# BRAIN_3.net
KiCad netlist of a schematic drawn in EAGLE
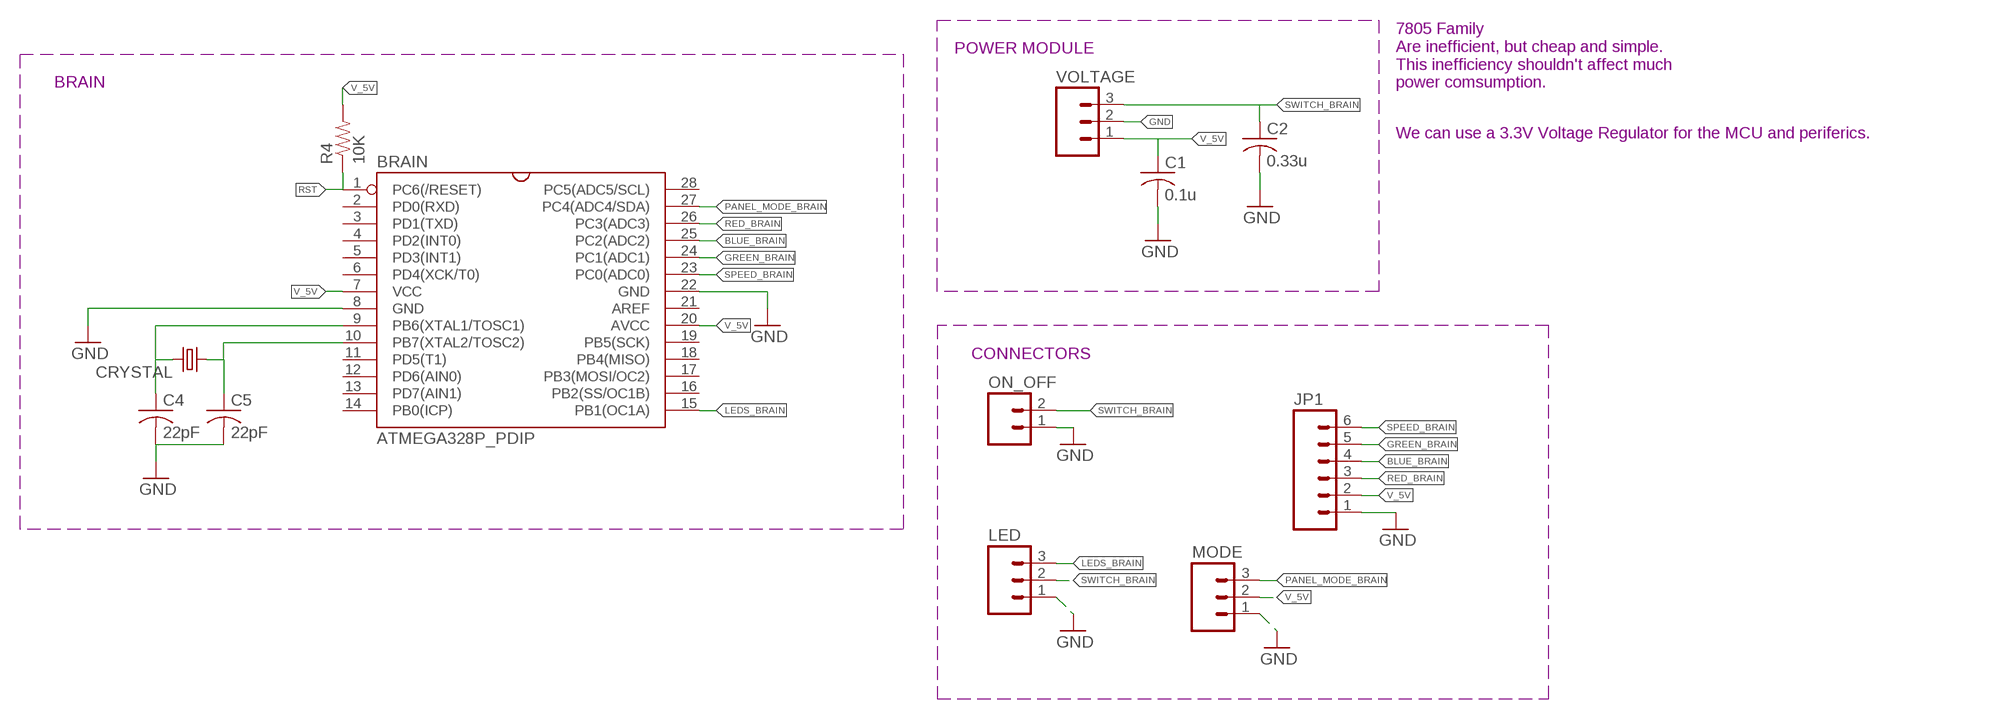
[diagram p0: schematic, sheet 1]

(export (version "E")
  (design (tool "Eeschema 10.0.6"))
  (components
    (comp (ref "BRAIN")
      (value "ATMEGA328P_PDIP")
      (footprint "eagle-import:DIL-28-3")
      (libsource (lib "eagle-import") (part "ATMEGA328P_PDIP"))
    )
    (comp (ref "C1")
      (value "0.1u")
      (footprint "eagle-import:C025-025X050")
      (libsource (lib "eagle-import") (part "C-US025-025X050"))
    )
    (comp (ref "C2")
      (value "0.33u")
      (footprint "eagle-import:C025-025X050")
      (libsource (lib "eagle-import") (part "C-US025-025X050"))
    )
    (comp (ref "C4")
      (value "22pF")
      (footprint "eagle-import:C025-024X044")
      (libsource (lib "eagle-import") (part "C-US025-024X044"))
    )
    (comp (ref "C5")
      (value "22pF")
      (footprint "eagle-import:C025-024X044")
      (libsource (lib "eagle-import") (part "C-US025-024X044"))
    )
    (comp (ref "CRYSTAL")
      (value "CRYSTALHC49US")
      (footprint "eagle-import:HC49US")
      (libsource (lib "eagle-import") (part "CRYSTALHC49US"))
    )
    (comp (ref "JP1")
      (value "M06NO_SILK_FEMALE_PTH")
      (footprint "eagle-import:1X06_NO_SILK")
      (libsource (lib "eagle-import") (part "M06NO_SILK_FEMALE_PTH"))
    )
    (comp (ref "LED")
      (value "M03PTH")
      (footprint "eagle-import:1X03")
      (libsource (lib "eagle-import") (part "M03PTH"))
    )
    (comp (ref "MODE")
      (value "M03PTH")
      (footprint "eagle-import:1X03")
      (libsource (lib "eagle-import") (part "M03PTH"))
    )
    (comp (ref "ON_OFF")
      (value "M02PTH")
      (footprint "eagle-import:1X02")
      (libsource (lib "eagle-import") (part "M02PTH"))
    )
    (comp (ref "R4")
      (value "10K")
      (footprint "eagle-import:AXIAL-0.3")
      (libsource (lib "eagle-import") (part "RESISTORAXIAL-0.3"))
    )
    (comp (ref "VOLTAGE")
      (value "M03PTH")
      (footprint "eagle-import:1X03")
      (libsource (lib "eagle-import") (part "M03PTH"))
    )
  )
  (nets
    (net (code "1") (name "BLUE_BRAIN") (class "Default")
      (node (ref "BRAIN") (pin "25") (pinfunction "PC2(ADC2)_25") (pintype "bidirectional"))
      (node (ref "JP1") (pin "4") (pinfunction "4_4") (pintype "passive"))
    )
    (net (code "2") (name "GND") (class "Default")
      (node (ref "BRAIN") (pin "22") (pinfunction "GND_22") (pintype "bidirectional"))
      (node (ref "BRAIN") (pin "8") (pinfunction "GND_8") (pintype "bidirectional"))
      (node (ref "C1") (pin "2") (pinfunction "2_2") (pintype "passive"))
      (node (ref "C2") (pin "2") (pinfunction "2_2") (pintype "passive"))
      (node (ref "C4") (pin "2") (pinfunction "2_2") (pintype "passive"))
      (node (ref "C5") (pin "2") (pinfunction "2_2") (pintype "passive"))
      (node (ref "JP1") (pin "1") (pinfunction "1_1") (pintype "passive"))
      (node (ref "LED") (pin "1") (pinfunction "1_1") (pintype "passive"))
      (node (ref "MODE") (pin "1") (pinfunction "1_1") (pintype "passive"))
      (node (ref "ON_OFF") (pin "1") (pinfunction "1_1") (pintype "passive"))
      (node (ref "VOLTAGE") (pin "2") (pinfunction "2_2") (pintype "passive"))
    )
    (net (code "3") (name "GREEN_BRAIN") (class "Default")
      (node (ref "BRAIN") (pin "24") (pinfunction "PC1(ADC1)_24") (pintype "bidirectional"))
      (node (ref "JP1") (pin "5") (pinfunction "5_5") (pintype "passive"))
    )
    (net (code "4") (name "LEDS_BRAIN") (class "Default")
      (node (ref "BRAIN") (pin "15") (pinfunction "PB1(OC1A)_15") (pintype "bidirectional"))
      (node (ref "LED") (pin "3") (pinfunction "3_3") (pintype "passive"))
    )
    (net (code "5") (name "Net-(BRAIN-PB6(XTAL1{slash}TOSC1))") (class "Default")
      (node (ref "BRAIN") (pin "9") (pinfunction "PB6(XTAL1/TOSC1)_9") (pintype "bidirectional"))
      (node (ref "C4") (pin "1") (pinfunction "1_1") (pintype "passive"))
      (node (ref "CRYSTAL") (pin "2") (pinfunction "2_2") (pintype "passive"))
    )
    (net (code "6") (name "Net-(BRAIN-PB7(XTAL2{slash}TOSC2))") (class "Default")
      (node (ref "BRAIN") (pin "10") (pinfunction "PB7(XTAL2/TOSC2)_10") (pintype "bidirectional"))
      (node (ref "C5") (pin "1") (pinfunction "1_1") (pintype "passive"))
      (node (ref "CRYSTAL") (pin "1") (pinfunction "1_1") (pintype "passive"))
    )
    (net (code "7") (name "PANEL_MODE_BRAIN") (class "Default")
      (node (ref "BRAIN") (pin "27") (pinfunction "PC4(ADC4/SDA)_27") (pintype "bidirectional"))
      (node (ref "MODE") (pin "3") (pinfunction "3_3") (pintype "passive"))
    )
    (net (code "8") (name "RED_BRAIN") (class "Default")
      (node (ref "BRAIN") (pin "26") (pinfunction "PC3(ADC3)_26") (pintype "bidirectional"))
      (node (ref "JP1") (pin "3") (pinfunction "3_3") (pintype "passive"))
    )
    (net (code "9") (name "RST") (class "Default")
      (node (ref "BRAIN") (pin "1") (pinfunction "PC6(/RESET)_1") (pintype "bidirectional"))
      (node (ref "R4") (pin "P$1") (pinfunction "1_P$1") (pintype "passive"))
    )
    (net (code "10") (name "SPEED_BRAIN") (class "Default")
      (node (ref "BRAIN") (pin "23") (pinfunction "PC0(ADC0)_23") (pintype "bidirectional"))
      (node (ref "JP1") (pin "6") (pinfunction "6_6") (pintype "passive"))
    )
    (net (code "11") (name "SWITCH_BRAIN") (class "Default")
      (node (ref "C2") (pin "1") (pinfunction "1_1") (pintype "passive"))
      (node (ref "LED") (pin "2") (pinfunction "2_2") (pintype "passive"))
      (node (ref "ON_OFF") (pin "2") (pinfunction "2_2") (pintype "passive"))
      (node (ref "VOLTAGE") (pin "3") (pinfunction "3_3") (pintype "passive"))
    )
    (net (code "12") (name "V_5V") (class "Default")
      (node (ref "BRAIN") (pin "20") (pinfunction "AVCC_20") (pintype "bidirectional"))
      (node (ref "BRAIN") (pin "7") (pinfunction "VCC_7") (pintype "bidirectional"))
      (node (ref "C1") (pin "1") (pinfunction "1_1") (pintype "passive"))
      (node (ref "JP1") (pin "2") (pinfunction "2_2") (pintype "passive"))
      (node (ref "MODE") (pin "2") (pinfunction "2_2") (pintype "passive"))
      (node (ref "R4") (pin "P$2") (pinfunction "2_P$2") (pintype "passive"))
      (node (ref "VOLTAGE") (pin "1") (pinfunction "1_1") (pintype "passive"))
    )
    (net (code "13") (name "unconnected-(BRAIN-AREF-Pad21)") (class "Default")
      (node (ref "BRAIN") (pin "21") (pinfunction "AREF_21") (pintype "bidirectional"))
    )
    (net (code "14") (name "unconnected-(BRAIN-PB0(ICP)-Pad14)") (class "Default")
      (node (ref "BRAIN") (pin "14") (pinfunction "PB0(ICP)_14") (pintype "bidirectional"))
    )
    (net (code "15") (name "unconnected-(BRAIN-PB2(SS{slash}OC1B)-Pad16)") (class "Default")
      (node (ref "BRAIN") (pin "16") (pinfunction "PB2(SS/OC1B)_16") (pintype "bidirectional"))
    )
    (net (code "16") (name "unconnected-(BRAIN-PB3(MOSI{slash}OC2)-Pad17)") (class "Default")
      (node (ref "BRAIN") (pin "17") (pinfunction "PB3(MOSI/OC2)_17") (pintype "bidirectional"))
    )
    (net (code "17") (name "unconnected-(BRAIN-PB4(MISO)-Pad18)") (class "Default")
      (node (ref "BRAIN") (pin "18") (pinfunction "PB4(MISO)_18") (pintype "bidirectional"))
    )
    (net (code "18") (name "unconnected-(BRAIN-PB5(SCK)-Pad19)") (class "Default")
      (node (ref "BRAIN") (pin "19") (pinfunction "PB5(SCK)_19") (pintype "bidirectional"))
    )
    (net (code "19") (name "unconnected-(BRAIN-PC5(ADC5{slash}SCL)-Pad28)") (class "Default")
      (node (ref "BRAIN") (pin "28") (pinfunction "PC5(ADC5/SCL)_28") (pintype "bidirectional"))
    )
    (net (code "20") (name "unconnected-(BRAIN-PD0(RXD)-Pad2)") (class "Default")
      (node (ref "BRAIN") (pin "2") (pinfunction "PD0(RXD)_2") (pintype "bidirectional"))
    )
    (net (code "21") (name "unconnected-(BRAIN-PD1(TXD)-Pad3)") (class "Default")
      (node (ref "BRAIN") (pin "3") (pinfunction "PD1(TXD)_3") (pintype "bidirectional"))
    )
    (net (code "22") (name "unconnected-(BRAIN-PD2(INT0)-Pad4)") (class "Default")
      (node (ref "BRAIN") (pin "4") (pinfunction "PD2(INT0)_4") (pintype "bidirectional"))
    )
    (net (code "23") (name "unconnected-(BRAIN-PD3(INT1)-Pad5)") (class "Default")
      (node (ref "BRAIN") (pin "5") (pinfunction "PD3(INT1)_5") (pintype "bidirectional"))
    )
    (net (code "24") (name "unconnected-(BRAIN-PD4(XCK{slash}T0)-Pad6)") (class "Default")
      (node (ref "BRAIN") (pin "6") (pinfunction "PD4(XCK/T0)_6") (pintype "bidirectional"))
    )
    (net (code "25") (name "unconnected-(BRAIN-PD5(T1)-Pad11)") (class "Default")
      (node (ref "BRAIN") (pin "11") (pinfunction "PD5(T1)_11") (pintype "bidirectional"))
    )
    (net (code "26") (name "unconnected-(BRAIN-PD6(AIN0)-Pad12)") (class "Default")
      (node (ref "BRAIN") (pin "12") (pinfunction "PD6(AIN0)_12") (pintype "bidirectional"))
    )
    (net (code "27") (name "unconnected-(BRAIN-PD7(AIN1)-Pad13)") (class "Default")
      (node (ref "BRAIN") (pin "13") (pinfunction "PD7(AIN1)_13") (pintype "bidirectional"))
    )
  )
)
